# M_2_M-KEY.net
KiCad netlist of a schematic drawn in Altium Designer
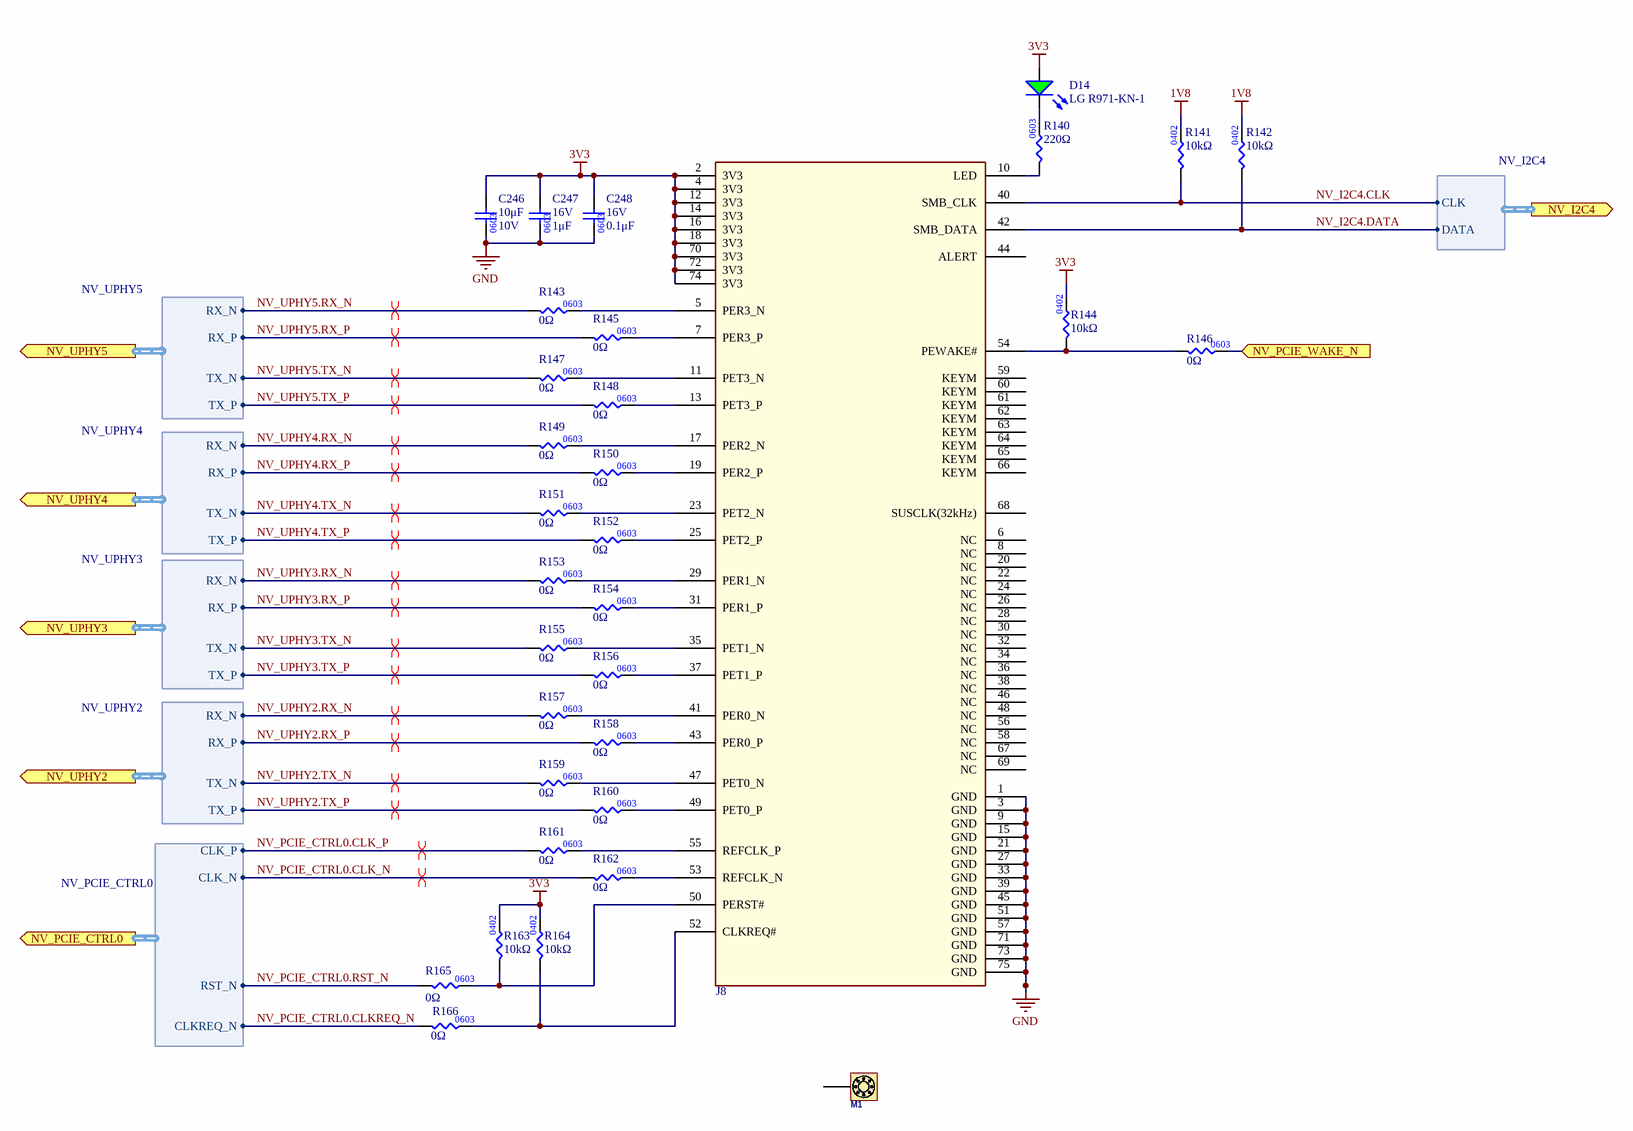
[diagram p0: M.2 M-KEY.SchDoc]

(export (version "E")
  (design (tool "Eeschema 10.0.6"))
  (components
    (comp (ref "C246")
      (value "10μF")
      (footprint "CAP0603")
      (description "CAP CER 10UF 10V X5R 0603")
      (fields (field (name "VOLTAGE RATING") "10V") (field (name "Comment") "CAP_10uF_10V_0603"))
      (libsource (lib "UWRT_Schematic_Library_2020") (part "CAP_10uF_10V_0603"))
    )
    (comp (ref "C247")
      (value "1μF")
      (footprint "CAP0603")
      (description "CAP CER 1UF 16V Y5V 0603")
      (fields (field (name "VOLTAGE RATING") "16V") (field (name "Comment") "CAP_1uF_16V_0603"))
      (libsource (lib "UWRT_Schematic_Library_2020") (part "CAP_1uF_16V_0603"))
    )
    (comp (ref "C248")
      (value "0.1μF")
      (footprint "CAP0603")
      (description "CAP CER 0.1UF 16V X7R 0603")
      (fields (field (name "VOLTAGE RATING") "16V") (field (name "Comment") "CAP_0.1uF_16V_0603"))
      (libsource (lib "UWRT_Schematic_Library_2020") (part "CAP_0.1uF_16V_0603"))
    )
    (comp (ref "D14")
      (value "LED_GREEN")
      (footprint "LED_0805_GREEN")
      (description "LED GREEN DIFFUSED 0805 SMD")
      (fields (field (name "MANUFACTURER PART NUMBER 1") "LG R971-KN-1"))
      (libsource (lib "UWRT_Schematic_Library_2020") (part "LED_GREEN"))
    )
    (comp (ref "J8")
      (value "CONN M.2 FEMALE 67POS 0.020 GOLD")
      (footprint "TE_2199119-4")
      (fields
        (field (name "MANUFACTURER") "TE Connectivity")
        (field (name "MANUFACTURER PART NUMBER") "1-2199119-5")
      )
      (libsource (lib "UWRT_Schematic_Library_2020") (part "CONN M.2 FEMALE 67POS 0.020 GOLD"))
    )
    (comp (ref "M1")
      (value "M3_SMT_STANDOFF_4-0MM")
      (footprint "M3_SMT_4-0MM")
      (description "ROUND STANDOFF M3X0.5 STEEL 4MM")
      (libsource (lib "UWRT_Schematic_Library_2020") (part "M3_SMT_STANDOFF_4-0MM"))
    )
    (comp (ref "R140")
      (value "220Ω")
      (footprint "RES0603")
      (description "RES 220 OHM 5% 1/10W 0603")
      (fields (field (name "Comment") "RES_220Ω_0603"))
      (libsource (lib "UWRT_Schematic_Library_2020") (part "RES_220Ω_0603_5%"))
    )
    (comp (ref "R141")
      (value "10kΩ")
      (footprint "RES0402")
      (description "RES SMD 10K OHM 1% 1/16W 0402")
      (fields (field (name "POWER") "0.063W, 1/16W") (field (name "TOLERANCE") "1%"))
      (libsource (lib "UWRT_Schematic_Library_2020") (part "RES_10kΩ_0402_1%"))
    )
    (comp (ref "R142")
      (value "10kΩ")
      (footprint "RES0402")
      (description "RES SMD 10K OHM 1% 1/16W 0402")
      (fields (field (name "POWER") "0.063W, 1/16W") (field (name "TOLERANCE") "1%"))
      (libsource (lib "UWRT_Schematic_Library_2020") (part "RES_10kΩ_0402_1%"))
    )
    (comp (ref "R143")
      (value "0Ω")
      (footprint "RES0603")
      (description "RES 0 OHM JUMPER 1/10W 0603")
      (fields (field (name "Comment") "RES_0Ω_0603"))
      (libsource (lib "UWRT_Schematic_Library_2020") (part "RES_0Ω_0603"))
    )
    (comp (ref "R144")
      (value "10kΩ")
      (footprint "RES0402")
      (description "RES SMD 10K OHM 1% 1/16W 0402")
      (fields (field (name "POWER") "0.063W, 1/16W") (field (name "TOLERANCE") "1%"))
      (libsource (lib "UWRT_Schematic_Library_2020") (part "RES_10kΩ_0402_1%"))
    )
    (comp (ref "R145")
      (value "0Ω")
      (footprint "RES0603")
      (description "RES 0 OHM JUMPER 1/10W 0603")
      (fields (field (name "Comment") "RES_0Ω_0603"))
      (libsource (lib "UWRT_Schematic_Library_2020") (part "RES_0Ω_0603"))
    )
    (comp (ref "R146")
      (value "0Ω")
      (footprint "RES0603")
      (description "RES 0 OHM JUMPER 1/10W 0603")
      (fields (field (name "Comment") "RES_0Ω_0603"))
      (libsource (lib "") (part "RES_0Ω_0603_1"))
    )
    (comp (ref "R147")
      (value "0Ω")
      (footprint "RES0603")
      (description "RES 0 OHM JUMPER 1/10W 0603")
      (fields (field (name "Comment") "RES_0Ω_0603"))
      (libsource (lib "UWRT_Schematic_Library_2020") (part "RES_0Ω_0603"))
    )
    (comp (ref "R148")
      (value "0Ω")
      (footprint "RES0603")
      (description "RES 0 OHM JUMPER 1/10W 0603")
      (fields (field (name "Comment") "RES_0Ω_0603"))
      (libsource (lib "UWRT_Schematic_Library_2020") (part "RES_0Ω_0603"))
    )
    (comp (ref "R149")
      (value "0Ω")
      (footprint "RES0603")
      (description "RES 0 OHM JUMPER 1/10W 0603")
      (fields (field (name "Comment") "RES_0Ω_0603"))
      (libsource (lib "UWRT_Schematic_Library_2020") (part "RES_0Ω_0603"))
    )
    (comp (ref "R150")
      (value "0Ω")
      (footprint "RES0603")
      (description "RES 0 OHM JUMPER 1/10W 0603")
      (fields (field (name "Comment") "RES_0Ω_0603"))
      (libsource (lib "UWRT_Schematic_Library_2020") (part "RES_0Ω_0603"))
    )
    (comp (ref "R151")
      (value "0Ω")
      (footprint "RES0603")
      (description "RES 0 OHM JUMPER 1/10W 0603")
      (fields (field (name "Comment") "RES_0Ω_0603"))
      (libsource (lib "UWRT_Schematic_Library_2020") (part "RES_0Ω_0603"))
    )
    (comp (ref "R152")
      (value "0Ω")
      (footprint "RES0603")
      (description "RES 0 OHM JUMPER 1/10W 0603")
      (fields (field (name "Comment") "RES_0Ω_0603"))
      (libsource (lib "UWRT_Schematic_Library_2020") (part "RES_0Ω_0603"))
    )
    (comp (ref "R153")
      (value "0Ω")
      (footprint "RES0603")
      (description "RES 0 OHM JUMPER 1/10W 0603")
      (fields (field (name "Comment") "RES_0Ω_0603"))
      (libsource (lib "UWRT_Schematic_Library_2020") (part "RES_0Ω_0603"))
    )
    (comp (ref "R154")
      (value "0Ω")
      (footprint "RES0603")
      (description "RES 0 OHM JUMPER 1/10W 0603")
      (fields (field (name "Comment") "RES_0Ω_0603"))
      (libsource (lib "UWRT_Schematic_Library_2020") (part "RES_0Ω_0603"))
    )
    (comp (ref "R155")
      (value "0Ω")
      (footprint "RES0603")
      (description "RES 0 OHM JUMPER 1/10W 0603")
      (fields (field (name "Comment") "RES_0Ω_0603"))
      (libsource (lib "UWRT_Schematic_Library_2020") (part "RES_0Ω_0603"))
    )
    (comp (ref "R156")
      (value "0Ω")
      (footprint "RES0603")
      (description "RES 0 OHM JUMPER 1/10W 0603")
      (fields (field (name "Comment") "RES_0Ω_0603"))
      (libsource (lib "UWRT_Schematic_Library_2020") (part "RES_0Ω_0603"))
    )
    (comp (ref "R157")
      (value "0Ω")
      (footprint "RES0603")
      (description "RES 0 OHM JUMPER 1/10W 0603")
      (fields (field (name "Comment") "RES_0Ω_0603"))
      (libsource (lib "UWRT_Schematic_Library_2020") (part "RES_0Ω_0603"))
    )
    (comp (ref "R158")
      (value "0Ω")
      (footprint "RES0603")
      (description "RES 0 OHM JUMPER 1/10W 0603")
      (fields (field (name "Comment") "RES_0Ω_0603"))
      (libsource (lib "UWRT_Schematic_Library_2020") (part "RES_0Ω_0603"))
    )
    (comp (ref "R159")
      (value "0Ω")
      (footprint "RES0603")
      (description "RES 0 OHM JUMPER 1/10W 0603")
      (fields (field (name "Comment") "RES_0Ω_0603"))
      (libsource (lib "UWRT_Schematic_Library_2020") (part "RES_0Ω_0603"))
    )
    (comp (ref "R160")
      (value "0Ω")
      (footprint "RES0603")
      (description "RES 0 OHM JUMPER 1/10W 0603")
      (fields (field (name "Comment") "RES_0Ω_0603"))
      (libsource (lib "UWRT_Schematic_Library_2020") (part "RES_0Ω_0603"))
    )
    (comp (ref "R161")
      (value "0Ω")
      (footprint "RES0603")
      (description "RES 0 OHM JUMPER 1/10W 0603")
      (fields (field (name "Comment") "RES_0Ω_0603"))
      (libsource (lib "UWRT_Schematic_Library_2020") (part "RES_0Ω_0603"))
    )
    (comp (ref "R162")
      (value "0Ω")
      (footprint "RES0603")
      (description "RES 0 OHM JUMPER 1/10W 0603")
      (fields (field (name "Comment") "RES_0Ω_0603"))
      (libsource (lib "UWRT_Schematic_Library_2020") (part "RES_0Ω_0603"))
    )
    (comp (ref "R163")
      (value "10kΩ")
      (footprint "RES0402")
      (description "RES SMD 10K OHM 1% 1/16W 0402")
      (fields (field (name "POWER") "0.063W, 1/16W") (field (name "TOLERANCE") "1%"))
      (libsource (lib "UWRT_Schematic_Library_2020") (part "RES_10kΩ_0402_1%"))
    )
    (comp (ref "R164")
      (value "10kΩ")
      (footprint "RES0402")
      (description "RES SMD 10K OHM 1% 1/16W 0402")
      (fields (field (name "POWER") "0.063W, 1/16W") (field (name "TOLERANCE") "1%"))
      (libsource (lib "UWRT_Schematic_Library_2020") (part "RES_10kΩ_0402_1%"))
    )
    (comp (ref "R165")
      (value "0Ω")
      (footprint "RES0603")
      (description "RES 0 OHM JUMPER 1/10W 0603")
      (fields (field (name "Comment") "RES_0Ω_0603"))
      (libsource (lib "") (part "RES_0Ω_0603_1"))
    )
    (comp (ref "R166")
      (value "0Ω")
      (footprint "RES0603")
      (description "RES 0 OHM JUMPER 1/10W 0603")
      (fields (field (name "Comment") "RES_0Ω_0603"))
      (libsource (lib "") (part "RES_0Ω_0603_1"))
    )
  )
  (nets
    (net (code "7") (name "/NV_I2C4.CLK") (class "Default")
      (node (ref "J8") (pin "40") (pinfunction "SMB_CLK_40") (pintype "passive"))
      (node (ref "R141") (pin "1") (pinfunction "1_1") (pintype "passive"))
    )
    (net (code "8") (name "/NV_I2C4.DATA") (class "Default")
      (node (ref "J8") (pin "42") (pinfunction "SMB_DATA_42") (pintype "passive"))
      (node (ref "R142") (pin "1") (pinfunction "1_1") (pintype "passive"))
    )
    (net (code "9") (name "/NV_PCIE_CTRL0.CLKREQ_N") (class "Default")
      (node (ref "R166") (pin "1") (pinfunction "1_1") (pintype "passive"))
    )
    (net (code "10") (name "/NV_PCIE_CTRL0.CLK_N") (class "Default")
      (node (ref "R162") (pin "1") (pinfunction "1_1") (pintype "passive"))
    )
    (net (code "11") (name "/NV_PCIE_CTRL0.CLK_P") (class "Default")
      (node (ref "R161") (pin "1") (pinfunction "1_1") (pintype "passive"))
    )
    (net (code "12") (name "/NV_PCIE_CTRL0.RST_N") (class "Default")
      (node (ref "R165") (pin "1") (pinfunction "1_1") (pintype "passive"))
    )
    (net (code "13") (name "/NV_PCIE_WAKE_N") (class "Default")
      (node (ref "R146") (pin "2") (pinfunction "2_2") (pintype "passive"))
    )
    (net (code "14") (name "/NV_UPHY2.RX_N") (class "Default")
      (node (ref "R157") (pin "1") (pinfunction "1_1") (pintype "passive"))
    )
    (net (code "15") (name "/NV_UPHY2.RX_P") (class "Default")
      (node (ref "R158") (pin "1") (pinfunction "1_1") (pintype "passive"))
    )
    (net (code "16") (name "/NV_UPHY2.TX_N") (class "Default")
      (node (ref "R159") (pin "1") (pinfunction "1_1") (pintype "passive"))
    )
    (net (code "17") (name "/NV_UPHY2.TX_P") (class "Default")
      (node (ref "R160") (pin "1") (pinfunction "1_1") (pintype "passive"))
    )
    (net (code "18") (name "/NV_UPHY3.RX_N") (class "Default")
      (node (ref "R153") (pin "1") (pinfunction "1_1") (pintype "passive"))
    )
    (net (code "19") (name "/NV_UPHY3.RX_P") (class "Default")
      (node (ref "R154") (pin "1") (pinfunction "1_1") (pintype "passive"))
    )
    (net (code "20") (name "/NV_UPHY3.TX_N") (class "Default")
      (node (ref "R155") (pin "1") (pinfunction "1_1") (pintype "passive"))
    )
    (net (code "21") (name "/NV_UPHY3.TX_P") (class "Default")
      (node (ref "R156") (pin "1") (pinfunction "1_1") (pintype "passive"))
    )
    (net (code "22") (name "/NV_UPHY4.RX_N") (class "Default")
      (node (ref "R149") (pin "1") (pinfunction "1_1") (pintype "passive"))
    )
    (net (code "23") (name "/NV_UPHY4.RX_P") (class "Default")
      (node (ref "R150") (pin "1") (pinfunction "1_1") (pintype "passive"))
    )
    (net (code "24") (name "/NV_UPHY4.TX_N") (class "Default")
      (node (ref "R151") (pin "1") (pinfunction "1_1") (pintype "passive"))
    )
    (net (code "25") (name "/NV_UPHY4.TX_P") (class "Default")
      (node (ref "R152") (pin "1") (pinfunction "1_1") (pintype "passive"))
    )
    (net (code "26") (name "/NV_UPHY5.RX_N") (class "Default")
      (node (ref "R143") (pin "1") (pinfunction "1_1") (pintype "passive"))
    )
    (net (code "27") (name "/NV_UPHY5.RX_P") (class "Default")
      (node (ref "R145") (pin "1") (pinfunction "1_1") (pintype "passive"))
    )
    (net (code "28") (name "/NV_UPHY5.TX_N") (class "Default")
      (node (ref "R147") (pin "1") (pinfunction "1_1") (pintype "passive"))
    )
    (net (code "29") (name "/NV_UPHY5.TX_P") (class "Default")
      (node (ref "R148") (pin "1") (pinfunction "1_1") (pintype "passive"))
    )
    (net (code "36") (name "1V8") (class "Default")
      (node (ref "R141") (pin "2") (pinfunction "2_2") (pintype "passive"))
      (node (ref "R142") (pin "2") (pinfunction "2_2") (pintype "passive"))
    )
    (net (code "37") (name "3V3") (class "Default")
      (node (ref "C246") (pin "2") (pinfunction "2_2") (pintype "passive"))
      (node (ref "C247") (pin "2") (pinfunction "2_2") (pintype "passive"))
      (node (ref "C248") (pin "2") (pinfunction "2_2") (pintype "passive"))
      (node (ref "D14") (pin "1") (pinfunction "A_1") (pintype "passive"))
      (node (ref "J8") (pin "12") (pinfunction "3V3_12") (pintype "passive"))
      (node (ref "J8") (pin "14") (pinfunction "3V3_14") (pintype "passive"))
      (node (ref "J8") (pin "16") (pinfunction "3V3_16") (pintype "passive"))
      (node (ref "J8") (pin "18") (pinfunction "3V3_18") (pintype "passive"))
      (node (ref "J8") (pin "2") (pinfunction "3V3_2") (pintype "passive"))
      (node (ref "J8") (pin "4") (pinfunction "3V3_4") (pintype "passive"))
      (node (ref "J8") (pin "70") (pinfunction "3V3_70") (pintype "passive"))
      (node (ref "J8") (pin "72") (pinfunction "3V3_72") (pintype "passive"))
      (node (ref "J8") (pin "74") (pinfunction "3V3_74") (pintype "passive"))
      (node (ref "R144") (pin "2") (pinfunction "2_2") (pintype "passive"))
      (node (ref "R163") (pin "2") (pinfunction "2_2") (pintype "passive"))
      (node (ref "R164") (pin "2") (pinfunction "2_2") (pintype "passive"))
    )
    (net (code "38") (name "GND") (class "Default")
      (node (ref "C246") (pin "1") (pinfunction "1_1") (pintype "passive"))
      (node (ref "C247") (pin "1") (pinfunction "1_1") (pintype "passive"))
      (node (ref "C248") (pin "1") (pinfunction "1_1") (pintype "passive"))
      (node (ref "J8") (pin "1") (pinfunction "GND_1") (pintype "passive"))
      (node (ref "J8") (pin "15") (pinfunction "GND_15") (pintype "passive"))
      (node (ref "J8") (pin "21") (pinfunction "GND_21") (pintype "passive"))
      (node (ref "J8") (pin "27") (pinfunction "GND_27") (pintype "passive"))
      (node (ref "J8") (pin "3") (pinfunction "GND_3") (pintype "passive"))
      (node (ref "J8") (pin "33") (pinfunction "GND_33") (pintype "passive"))
      (node (ref "J8") (pin "39") (pinfunction "GND_39") (pintype "passive"))
      (node (ref "J8") (pin "45") (pinfunction "GND_45") (pintype "passive"))
      (node (ref "J8") (pin "51") (pinfunction "GND_51") (pintype "passive"))
      (node (ref "J8") (pin "57") (pinfunction "GND_57") (pintype "passive"))
      (node (ref "J8") (pin "71") (pinfunction "GND_71") (pintype "passive"))
      (node (ref "J8") (pin "73") (pinfunction "GND_73") (pintype "passive"))
      (node (ref "J8") (pin "75") (pinfunction "GND_75") (pintype "passive"))
      (node (ref "J8") (pin "9") (pinfunction "GND_9") (pintype "passive"))
    )
    (net (code "39") (name "Net-(D14-K)") (class "Default")
      (node (ref "D14") (pin "2") (pinfunction "K_2") (pintype "passive"))
      (node (ref "R140") (pin "2") (pinfunction "2_2") (pintype "passive"))
    )
    (net (code "40") (name "Net-(J8-CLKREQ#)") (class "Default")
      (node (ref "J8") (pin "52") (pinfunction "CLKREQ#_52") (pintype "passive"))
      (node (ref "R164") (pin "1") (pinfunction "1_1") (pintype "passive"))
      (node (ref "R166") (pin "2") (pinfunction "2_2") (pintype "passive"))
    )
    (net (code "41") (name "Net-(J8-LED)") (class "Default")
      (node (ref "J8") (pin "10") (pinfunction "LED_10") (pintype "passive"))
      (node (ref "R140") (pin "1") (pinfunction "1_1") (pintype "passive"))
    )
    (net (code "42") (name "Net-(J8-PER0_N)") (class "Default")
      (node (ref "J8") (pin "41") (pinfunction "PER0_N_41") (pintype "passive"))
      (node (ref "R157") (pin "2") (pinfunction "2_2") (pintype "passive"))
    )
    (net (code "43") (name "Net-(J8-PER0_P)") (class "Default")
      (node (ref "J8") (pin "43") (pinfunction "PER0_P_43") (pintype "passive"))
      (node (ref "R158") (pin "2") (pinfunction "2_2") (pintype "passive"))
    )
    (net (code "44") (name "Net-(J8-PER1_N)") (class "Default")
      (node (ref "J8") (pin "29") (pinfunction "PER1_N_29") (pintype "passive"))
      (node (ref "R153") (pin "2") (pinfunction "2_2") (pintype "passive"))
    )
    (net (code "45") (name "Net-(J8-PER1_P)") (class "Default")
      (node (ref "J8") (pin "31") (pinfunction "PER1_P_31") (pintype "passive"))
      (node (ref "R154") (pin "2") (pinfunction "2_2") (pintype "passive"))
    )
    (net (code "46") (name "Net-(J8-PER2_N)") (class "Default")
      (node (ref "J8") (pin "17") (pinfunction "PER2_N_17") (pintype "passive"))
      (node (ref "R149") (pin "2") (pinfunction "2_2") (pintype "passive"))
    )
    (net (code "47") (name "Net-(J8-PER2_P)") (class "Default")
      (node (ref "J8") (pin "19") (pinfunction "PER2_P_19") (pintype "passive"))
      (node (ref "R150") (pin "2") (pinfunction "2_2") (pintype "passive"))
    )
    (net (code "48") (name "Net-(J8-PER3_N)") (class "Default")
      (node (ref "J8") (pin "5") (pinfunction "PER3_N_5") (pintype "passive"))
      (node (ref "R143") (pin "2") (pinfunction "2_2") (pintype "passive"))
    )
    (net (code "49") (name "Net-(J8-PER3_P)") (class "Default")
      (node (ref "J8") (pin "7") (pinfunction "PER3_P_7") (pintype "passive"))
      (node (ref "R145") (pin "2") (pinfunction "2_2") (pintype "passive"))
    )
    (net (code "50") (name "Net-(J8-PERST#)") (class "Default")
      (node (ref "J8") (pin "50") (pinfunction "PERST#_50") (pintype "passive"))
      (node (ref "R163") (pin "1") (pinfunction "1_1") (pintype "passive"))
      (node (ref "R165") (pin "2") (pinfunction "2_2") (pintype "passive"))
    )
    (net (code "51") (name "Net-(J8-PET0_N)") (class "Default")
      (node (ref "J8") (pin "47") (pinfunction "PET0_N_47") (pintype "passive"))
      (node (ref "R159") (pin "2") (pinfunction "2_2") (pintype "passive"))
    )
    (net (code "52") (name "Net-(J8-PET0_P)") (class "Default")
      (node (ref "J8") (pin "49") (pinfunction "PET0_P_49") (pintype "passive"))
      (node (ref "R160") (pin "2") (pinfunction "2_2") (pintype "passive"))
    )
    (net (code "53") (name "Net-(J8-PET1_N)") (class "Default")
      (node (ref "J8") (pin "35") (pinfunction "PET1_N_35") (pintype "passive"))
      (node (ref "R155") (pin "2") (pinfunction "2_2") (pintype "passive"))
    )
    (net (code "54") (name "Net-(J8-PET1_P)") (class "Default")
      (node (ref "J8") (pin "37") (pinfunction "PET1_P_37") (pintype "passive"))
      (node (ref "R156") (pin "2") (pinfunction "2_2") (pintype "passive"))
    )
    (net (code "55") (name "Net-(J8-PET2_N)") (class "Default")
      (node (ref "J8") (pin "23") (pinfunction "PET2_N_23") (pintype "passive"))
      (node (ref "R151") (pin "2") (pinfunction "2_2") (pintype "passive"))
    )
    (net (code "56") (name "Net-(J8-PET2_P)") (class "Default")
      (node (ref "J8") (pin "25") (pinfunction "PET2_P_25") (pintype "passive"))
      (node (ref "R152") (pin "2") (pinfunction "2_2") (pintype "passive"))
    )
    (net (code "57") (name "Net-(J8-PET3_N)") (class "Default")
      (node (ref "J8") (pin "11") (pinfunction "PET3_N_11") (pintype "passive"))
      (node (ref "R147") (pin "2") (pinfunction "2_2") (pintype "passive"))
    )
    (net (code "58") (name "Net-(J8-PET3_P)") (class "Default")
      (node (ref "J8") (pin "13") (pinfunction "PET3_P_13") (pintype "passive"))
      (node (ref "R148") (pin "2") (pinfunction "2_2") (pintype "passive"))
    )
    (net (code "59") (name "Net-(J8-PEWAKE#)") (class "Default")
      (node (ref "J8") (pin "54") (pinfunction "PEWAKE#_54") (pintype "passive"))
      (node (ref "R144") (pin "1") (pinfunction "1_1") (pintype "passive"))
      (node (ref "R146") (pin "1") (pinfunction "1_1") (pintype "passive"))
    )
    (net (code "60") (name "Net-(J8-REFCLK_N)") (class "Default")
      (node (ref "J8") (pin "53") (pinfunction "REFCLK_N_53") (pintype "passive"))
      (node (ref "R162") (pin "2") (pinfunction "2_2") (pintype "passive"))
    )
    (net (code "61") (name "Net-(J8-REFCLK_P)") (class "Default")
      (node (ref "J8") (pin "55") (pinfunction "REFCLK_P_55") (pintype "passive"))
      (node (ref "R161") (pin "2") (pinfunction "2_2") (pintype "passive"))
    )
    (net (code "62") (name "unconnected-(J8-ALERT-Pad44)") (class "Default")
      (node (ref "J8") (pin "44") (pinfunction "ALERT_44") (pintype "passive"))
    )
    (net (code "63") (name "unconnected-(J8-KEYM-Pad59)") (class "Default")
      (node (ref "J8") (pin "59") (pinfunction "KEYM_59") (pintype "passive"))
    )
    (net (code "64") (name "unconnected-(J8-KEYM-Pad60)") (class "Default")
      (node (ref "J8") (pin "60") (pinfunction "KEYM_60") (pintype "passive"))
    )
    (net (code "65") (name "unconnected-(J8-KEYM-Pad61)") (class "Default")
      (node (ref "J8") (pin "61") (pinfunction "KEYM_61") (pintype "passive"))
    )
    (net (code "66") (name "unconnected-(J8-KEYM-Pad62)") (class "Default")
      (node (ref "J8") (pin "62") (pinfunction "KEYM_62") (pintype "passive"))
    )
    (net (code "67") (name "unconnected-(J8-KEYM-Pad63)") (class "Default")
      (node (ref "J8") (pin "63") (pinfunction "KEYM_63") (pintype "passive"))
    )
    (net (code "68") (name "unconnected-(J8-KEYM-Pad64)") (class "Default")
      (node (ref "J8") (pin "64") (pinfunction "KEYM_64") (pintype "passive"))
    )
    (net (code "69") (name "unconnected-(J8-KEYM-Pad65)") (class "Default")
      (node (ref "J8") (pin "65") (pinfunction "KEYM_65") (pintype "passive"))
    )
    (net (code "70") (name "unconnected-(J8-KEYM-Pad66)") (class "Default")
      (node (ref "J8") (pin "66") (pinfunction "KEYM_66") (pintype "passive"))
    )
    (net (code "71") (name "unconnected-(J8-NC-Pad6)") (class "Default")
      (node (ref "J8") (pin "6") (pinfunction "NC_6") (pintype "passive"))
    )
    (net (code "72") (name "unconnected-(J8-NC-Pad8)") (class "Default")
      (node (ref "J8") (pin "8") (pinfunction "NC_8") (pintype "passive"))
    )
    (net (code "73") (name "unconnected-(J8-NC-Pad20)") (class "Default")
      (node (ref "J8") (pin "20") (pinfunction "NC_20") (pintype "passive"))
    )
    (net (code "74") (name "unconnected-(J8-NC-Pad22)") (class "Default")
      (node (ref "J8") (pin "22") (pinfunction "NC_22") (pintype "passive"))
    )
    (net (code "75") (name "unconnected-(J8-NC-Pad24)") (class "Default")
      (node (ref "J8") (pin "24") (pinfunction "NC_24") (pintype "passive"))
    )
    (net (code "76") (name "unconnected-(J8-NC-Pad26)") (class "Default")
      (node (ref "J8") (pin "26") (pinfunction "NC_26") (pintype "passive"))
    )
    (net (code "77") (name "unconnected-(J8-NC-Pad28)") (class "Default")
      (node (ref "J8") (pin "28") (pinfunction "NC_28") (pintype "passive"))
    )
    (net (code "78") (name "unconnected-(J8-NC-Pad30)") (class "Default")
      (node (ref "J8") (pin "30") (pinfunction "NC_30") (pintype "passive"))
    )
    (net (code "79") (name "unconnected-(J8-NC-Pad32)") (class "Default")
      (node (ref "J8") (pin "32") (pinfunction "NC_32") (pintype "passive"))
    )
    (net (code "80") (name "unconnected-(J8-NC-Pad34)") (class "Default")
      (node (ref "J8") (pin "34") (pinfunction "NC_34") (pintype "passive"))
    )
    (net (code "81") (name "unconnected-(J8-NC-Pad36)") (class "Default")
      (node (ref "J8") (pin "36") (pinfunction "NC_36") (pintype "passive"))
    )
    (net (code "82") (name "unconnected-(J8-NC-Pad38)") (class "Default")
      (node (ref "J8") (pin "38") (pinfunction "NC_38") (pintype "passive"))
    )
    (net (code "83") (name "unconnected-(J8-NC-Pad46)") (class "Default")
      (node (ref "J8") (pin "46") (pinfunction "NC_46") (pintype "passive"))
    )
    (net (code "84") (name "unconnected-(J8-NC-Pad48)") (class "Default")
      (node (ref "J8") (pin "48") (pinfunction "NC_48") (pintype "passive"))
    )
    (net (code "85") (name "unconnected-(J8-NC-Pad56)") (class "Default")
      (node (ref "J8") (pin "56") (pinfunction "NC_56") (pintype "passive"))
    )
    (net (code "86") (name "unconnected-(J8-NC-Pad58)") (class "Default")
      (node (ref "J8") (pin "58") (pinfunction "NC_58") (pintype "passive"))
    )
    (net (code "87") (name "unconnected-(J8-NC-Pad67)") (class "Default")
      (node (ref "J8") (pin "67") (pinfunction "NC_67") (pintype "passive"))
    )
    (net (code "88") (name "unconnected-(J8-NC-Pad69)") (class "Default")
      (node (ref "J8") (pin "69") (pinfunction "NC_69") (pintype "passive"))
    )
    (net (code "89") (name "unconnected-(J8-SUSCLK(32kHz)-Pad68)") (class "Default")
      (node (ref "J8") (pin "68") (pinfunction "SUSCLK(32kHz)_68") (pintype "passive"))
    )
    (net (code "90") (name "unconnected-(M1-Pad0)") (class "Default")
      (node (ref "M1") (pin "0") (pinfunction "0_0") (pintype "passive"))
    )
  )
)
